# I2S_Mic_with_0805_resistors.net
KiCad netlist of a schematic drawn in EAGLE
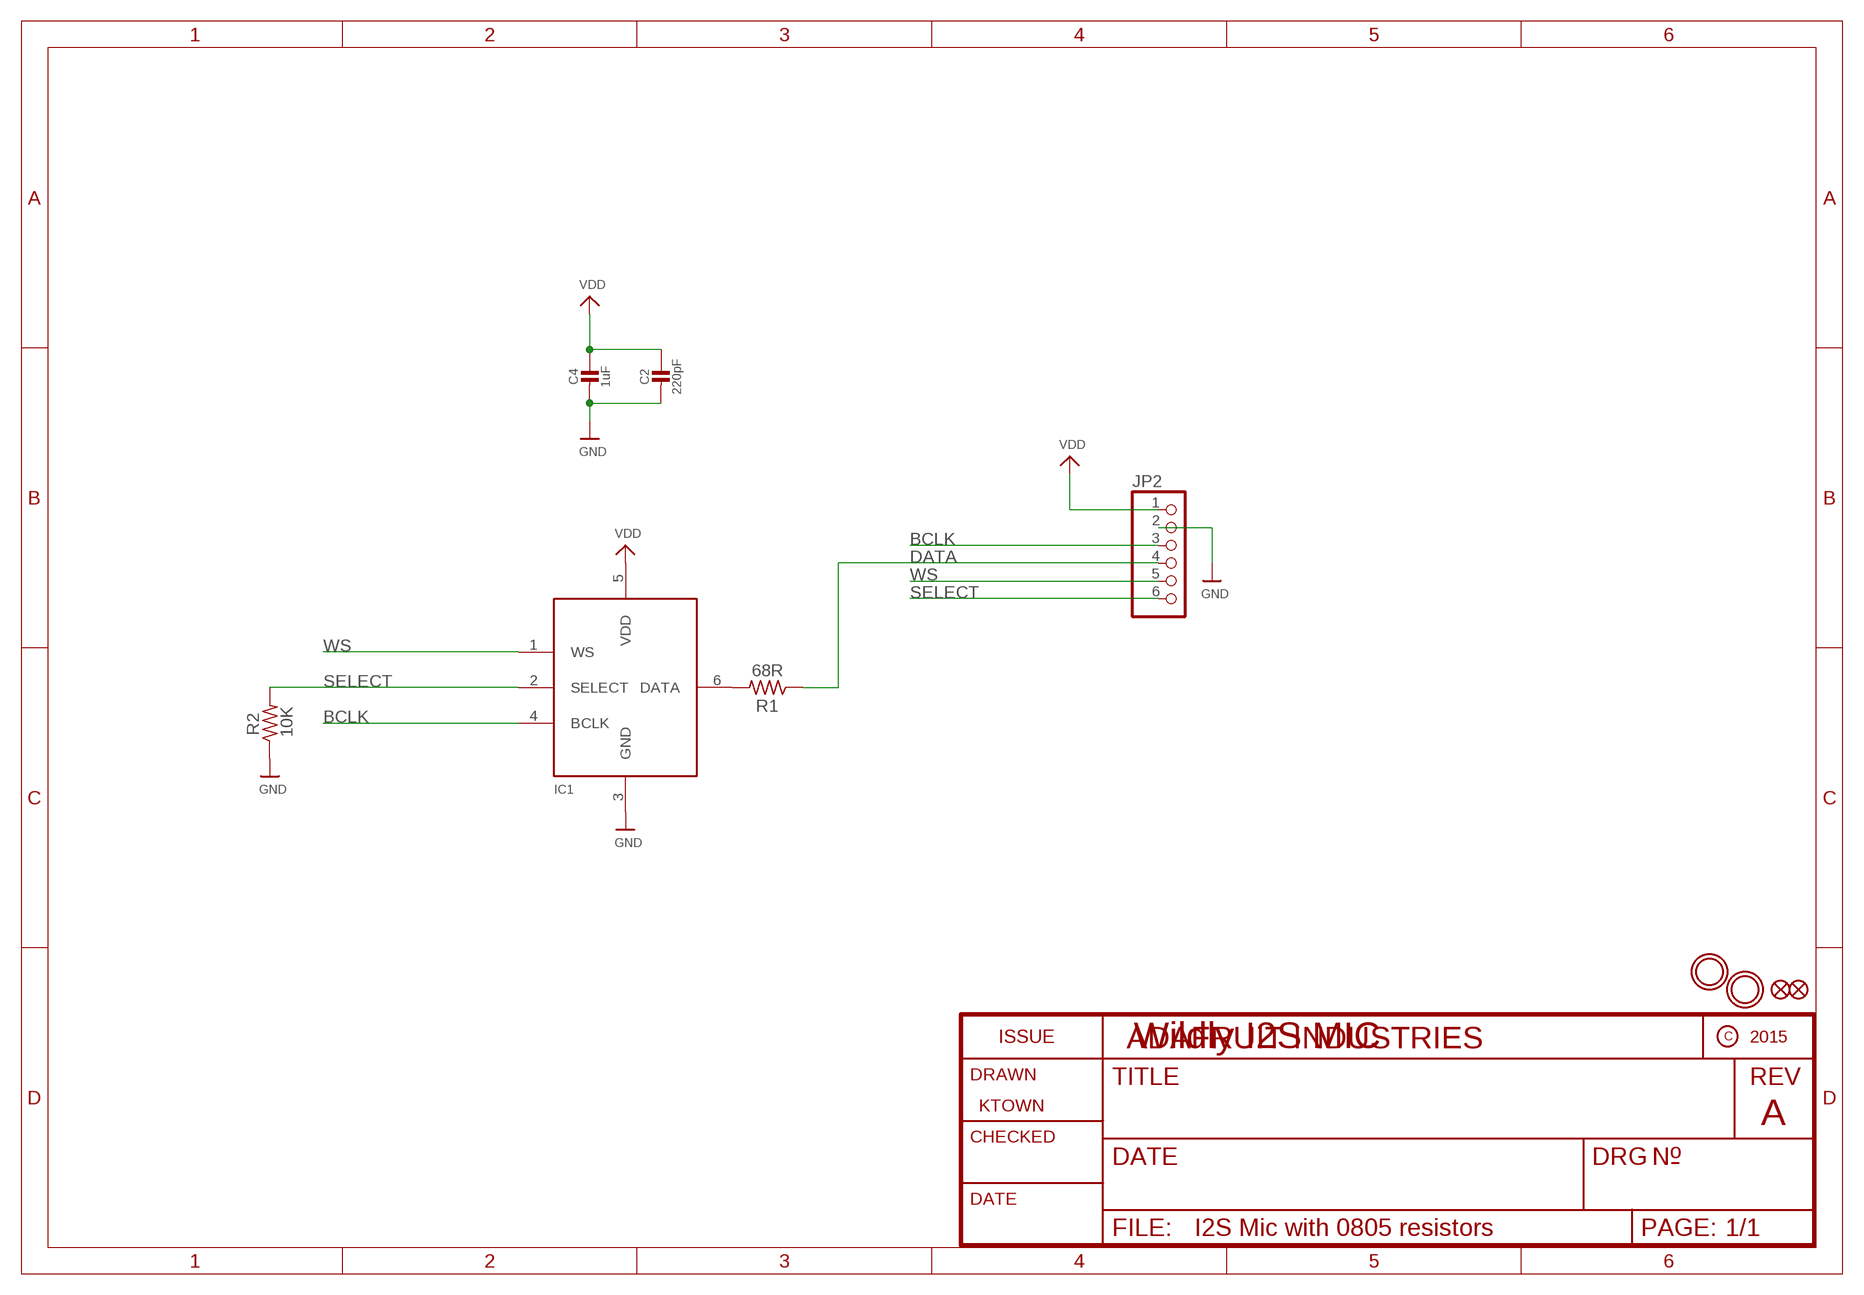
[diagram p0: schematic, sheet 1]

(export (version "E")
  (design (tool "Eeschema 10.0.6"))
  (components
    (comp (ref "C2")
      (value "220pF")
      (footprint "eagle-import:0805-NO")
      (libsource (lib "eagle-import") (part "CAP_CERAMIC0805-NOOUTLINE"))
    )
    (comp (ref "C4")
      (value "1uF")
      (footprint "eagle-import:0805-NO")
      (libsource (lib "eagle-import") (part "CAP_CERAMIC0805-NOOUTLINE"))
    )
    (comp (ref "FID1")
      (value "FIDUCIAL_1MM")
      (footprint "eagle-import:FIDUCIAL_1MM")
      (libsource (lib "eagle-import") (part "FIDUCIAL_1MM"))
    )
    (comp (ref "FID2")
      (value "FIDUCIAL_1MM")
      (footprint "eagle-import:FIDUCIAL_1MM")
      (libsource (lib "eagle-import") (part "FIDUCIAL_1MM"))
    )
    (comp (ref "IC1")
      (value "MIC_I2S_SPH0645")
      (footprint "eagle-import:SPH0645LM4H")
      (libsource (lib "eagle-import") (part "MIC_I2S_SPH0645"))
    )
    (comp (ref "JP2")
      (value "HEADER-1X6ROUND")
      (footprint "eagle-import:1X06_ROUND")
      (libsource (lib "eagle-import") (part "HEADER-1X6ROUND"))
    )
    (comp (ref "R1")
      (value "68R")
      (footprint "eagle-import:R0805")
      (libsource (lib "eagle-import") (part "R-US_R0805"))
    )
    (comp (ref "R2")
      (value "10K")
      (footprint "eagle-import:R0805")
      (libsource (lib "eagle-import") (part "R-US_R0805"))
    )
    (comp (ref "U$6")
      (value "MOUNTINGHOLE2.5")
      (footprint "eagle-import:MOUNTINGHOLE_2.5_PLATED")
      (libsource (lib "eagle-import") (part "MOUNTINGHOLE2.5"))
    )
    (comp (ref "U$12")
      (value "MOUNTINGHOLE2.5")
      (footprint "eagle-import:MOUNTINGHOLE_2.5_PLATED")
      (libsource (lib "eagle-import") (part "MOUNTINGHOLE2.5"))
    )
  )
  (nets
    (net (code "1") (name "/BCLK") (class "Default")
      (node (ref "IC1") (pin "4") (pinfunction "BCLK_4") (pintype "input"))
      (node (ref "JP2") (pin "3") (pinfunction "3_3") (pintype "passive"))
    )
    (net (code "2") (name "/DATA") (class "Default")
      (node (ref "JP2") (pin "4") (pinfunction "4_4") (pintype "passive"))
      (node (ref "R1") (pin "1") (pinfunction "1_1") (pintype "passive"))
    )
    (net (code "3") (name "/SELECT") (class "Default")
      (node (ref "IC1") (pin "2") (pinfunction "SELECT_2") (pintype "input"))
      (node (ref "JP2") (pin "6") (pinfunction "6_6") (pintype "passive"))
      (node (ref "R2") (pin "2") (pinfunction "2_2") (pintype "passive"))
    )
    (net (code "4") (name "/WS") (class "Default")
      (node (ref "IC1") (pin "1") (pinfunction "WS_1") (pintype "input"))
      (node (ref "JP2") (pin "5") (pinfunction "5_5") (pintype "passive"))
    )
    (net (code "5") (name "GND") (class "Default")
      (node (ref "C2") (pin "2") (pinfunction "2_2") (pintype "passive"))
      (node (ref "C4") (pin "2") (pinfunction "2_2") (pintype "passive"))
      (node (ref "IC1") (pin "3") (pinfunction "GND_3") (pintype "power_in"))
      (node (ref "JP2") (pin "2") (pinfunction "2_2") (pintype "passive"))
      (node (ref "R2") (pin "1") (pinfunction "1_1") (pintype "passive"))
    )
    (net (code "6") (name "Net-(IC1-DATA)") (class "Default")
      (node (ref "IC1") (pin "6") (pinfunction "DATA_6") (pintype "output"))
      (node (ref "R1") (pin "2") (pinfunction "2_2") (pintype "passive"))
    )
    (net (code "7") (name "VDD") (class "Default")
      (node (ref "C2") (pin "1") (pinfunction "1_1") (pintype "passive"))
      (node (ref "C4") (pin "1") (pinfunction "1_1") (pintype "passive"))
      (node (ref "IC1") (pin "5") (pinfunction "VDD_5") (pintype "power_in"))
      (node (ref "JP2") (pin "1") (pinfunction "1_1") (pintype "passive"))
    )
  )
)
